# 3.net
KiCad netlist of a schematic drawn in Altium Designer
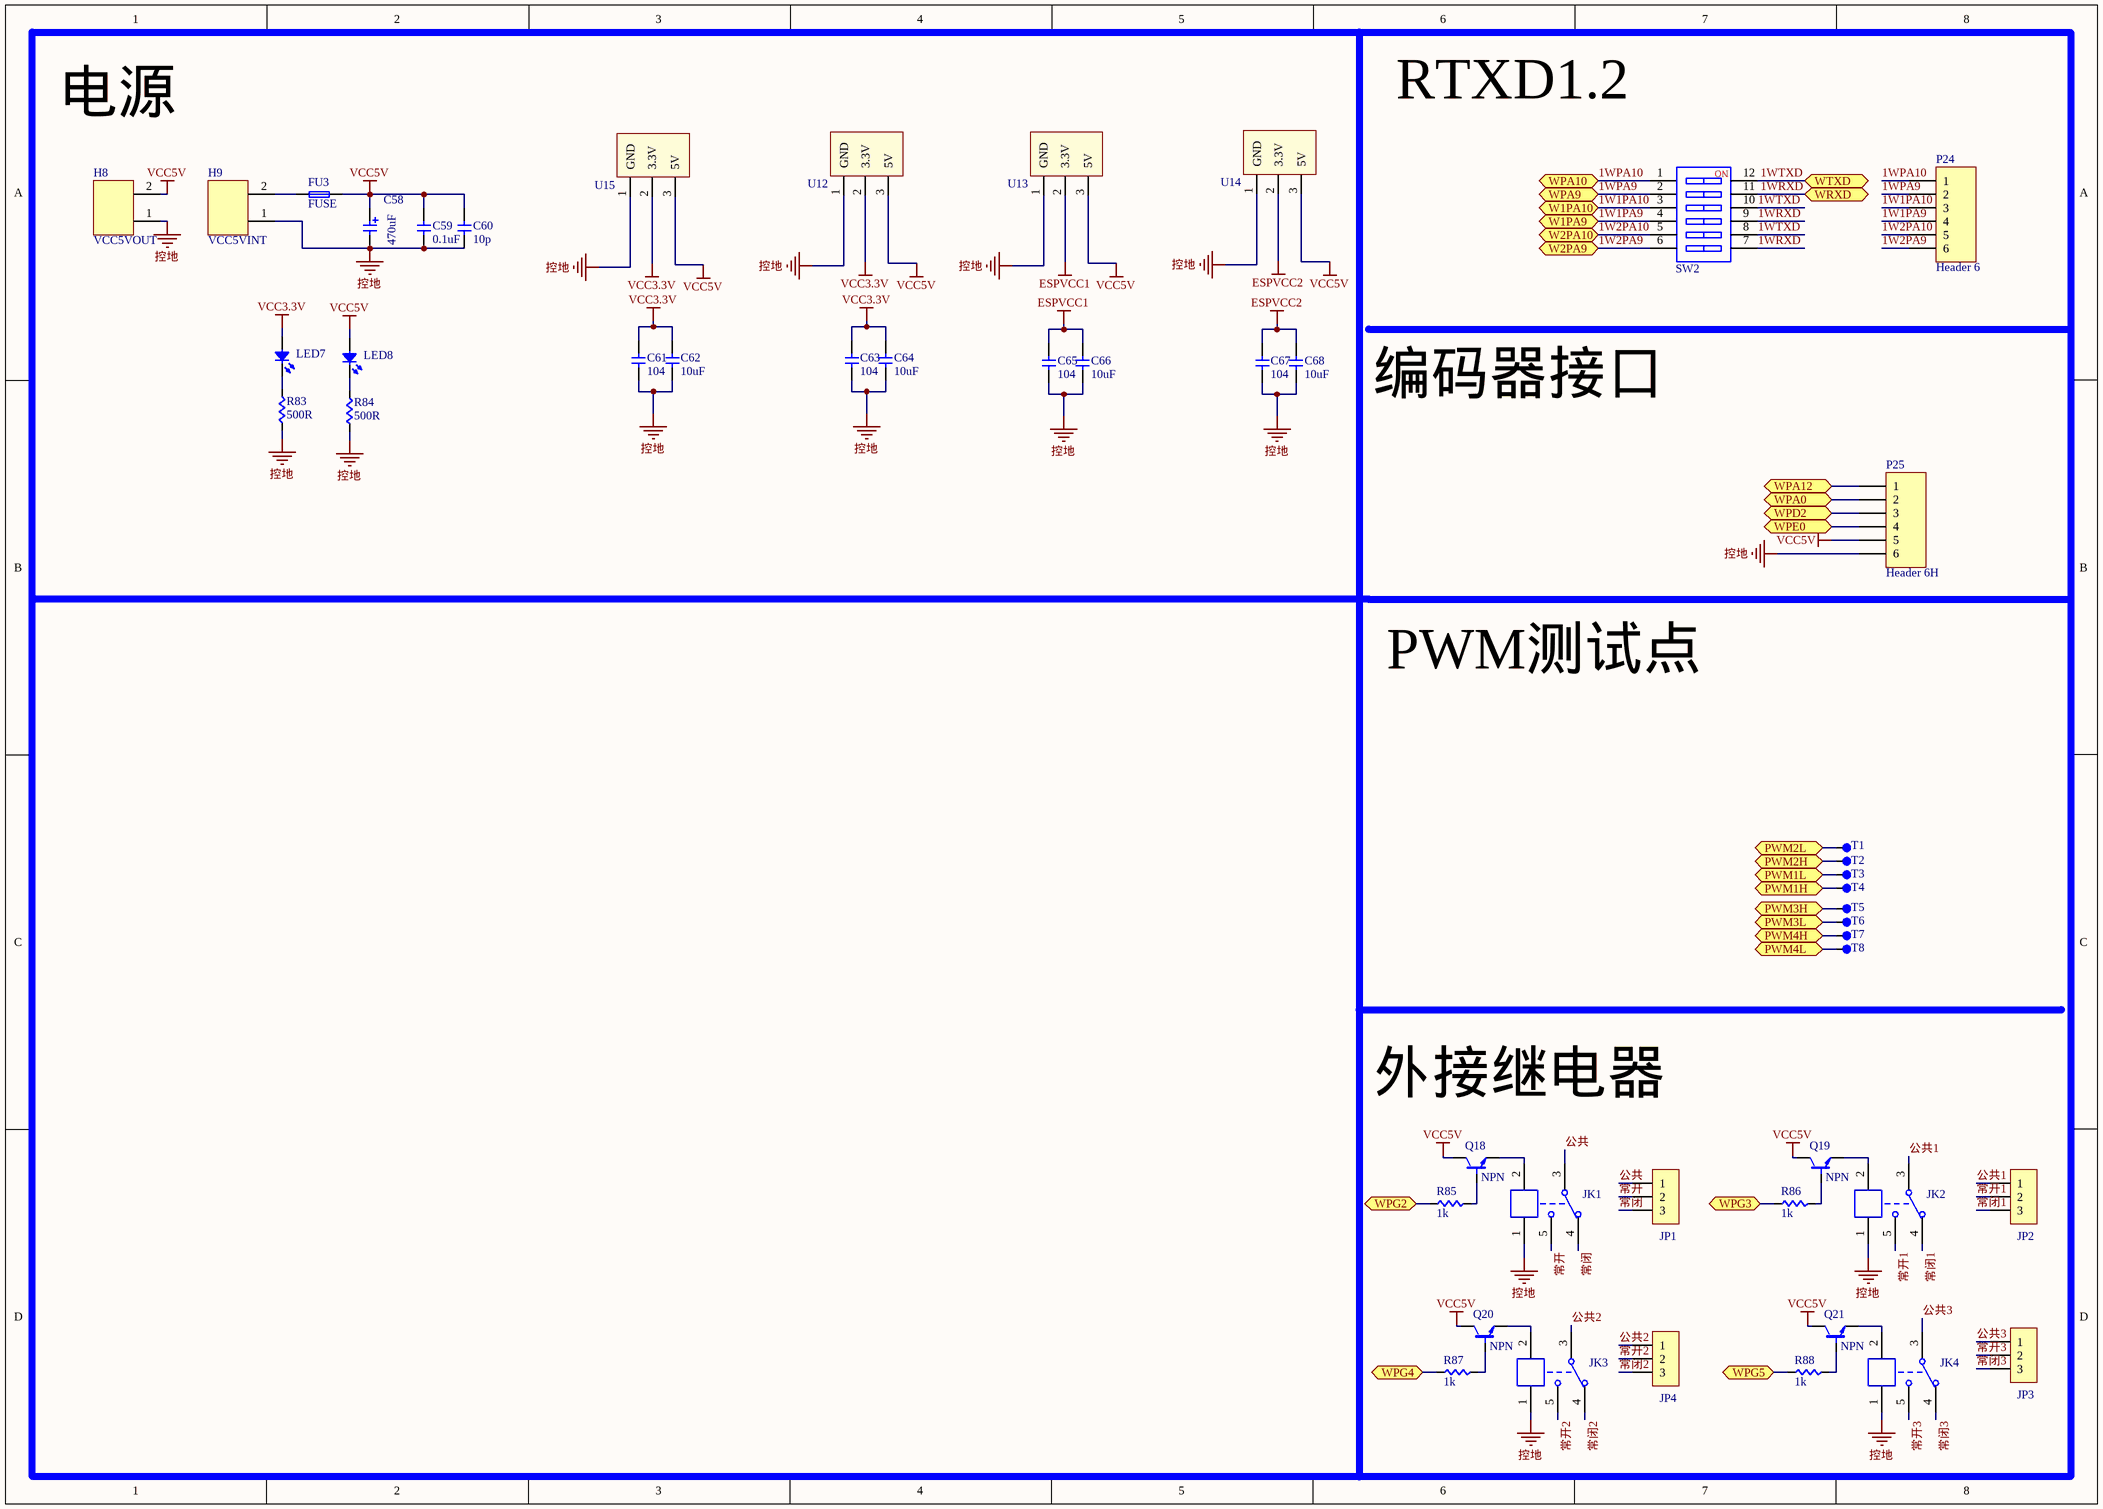
[diagram p0: 小车主板原理图3.SchDoc]

(export (version "E")
  (design (tool "Eeschema 10.0.6"))
  (components
    (comp (ref "C58")
      (value "470uF")
      (footprint "CD-8*8-2")
      (fields (field (name "PUBLISHER") "Altium Limited"))
      (libsource (lib "史福祥库") (part "C+"))
    )
    (comp (ref "C59") (value "0.1uF") (footprint "0805C") (libsource (lib "史福祥库") (part "C")))
    (comp (ref "C60") (value "10p") (footprint "0805C") (libsource (lib "史福祥库") (part "C")))
    (comp (ref "C61") (value "104") (footprint "0805C") (libsource (lib "史福祥库") (part "C")))
    (comp (ref "C62") (value "10uF") (footprint "0805C") (libsource (lib "史福祥库") (part "C")))
    (comp (ref "C63") (value "104") (footprint "0805C") (libsource (lib "史福祥库") (part "C")))
    (comp (ref "C64") (value "10uF") (footprint "0805C") (libsource (lib "史福祥库") (part "C")))
    (comp (ref "C65") (value "104") (footprint "0805C") (libsource (lib "史福祥库") (part "C")))
    (comp (ref "C66") (value "10uF") (footprint "0805C") (libsource (lib "史福祥库") (part "C")))
    (comp (ref "C67") (value "104") (footprint "0805C") (libsource (lib "史福祥库") (part "C")))
    (comp (ref "C68") (value "10uF") (footprint "0805C") (libsource (lib "史福祥库") (part "C")))
    (comp (ref "FU3") (value "FUSE") (footprint "1206") (libsource (lib "史福祥库") (part "FUSE")))
    (comp (ref "H8") (value "VCC5VOUT") (footprint "KF301接线端子") (libsource (lib "史福祥库") (part "KF301 接线端子")))
    (comp (ref "H9") (value "VCC5VINT") (footprint "KF301接线端子") (libsource (lib "史福祥库") (part "KF301 接线端子")))
    (comp (ref "JK1")
      (value "~")
      (footprint "SRD-C_B")
      (description "5V单路双控继电器")
      (fields (field (name "版权归属") "源创客"))
      (libsource (lib "继电器") (part "SRD-05VDC-SL-C"))
    )
    (comp (ref "JK2")
      (value "~")
      (footprint "SRD-C_B")
      (description "5V单路双控继电器")
      (fields (field (name "版权归属") "源创客"))
      (libsource (lib "继电器") (part "SRD-05VDC-SL-C"))
    )
    (comp (ref "JK3")
      (value "~")
      (footprint "SRD-C_B")
      (description "5V单路双控继电器")
      (fields (field (name "版权归属") "源创客"))
      (libsource (lib "继电器") (part "SRD-05VDC-SL-C"))
    )
    (comp (ref "JK4")
      (value "~")
      (footprint "SRD-C_B")
      (description "5V单路双控继电器")
      (fields (field (name "版权归属") "源创客"))
      (libsource (lib "继电器") (part "SRD-05VDC-SL-C"))
    )
    (comp (ref "JP1")
      (value "HDR-1X3")
      (footprint "KF301-3P")
      (description "3P接插件")
      (fields (field (name "版权归属") "源创客"))
      (libsource (lib "接插件") (part "Header 3"))
    )
    (comp (ref "JP2")
      (value "HDR-1X3")
      (footprint "KF301-3P")
      (description "3P接插件")
      (fields (field (name "版权归属") "源创客"))
      (libsource (lib "接插件") (part "Header 3"))
    )
    (comp (ref "JP3")
      (value "HDR-1X3")
      (footprint "KF301-3P")
      (description "3P接插件")
      (fields (field (name "版权归属") "源创客"))
      (libsource (lib "接插件") (part "Header 3"))
    )
    (comp (ref "JP4")
      (value "HDR-1X3")
      (footprint "KF301-3P")
      (description "3P接插件")
      (fields (field (name "版权归属") "源创客"))
      (libsource (lib "接插件") (part "Header 3"))
    )
    (comp (ref "LED7")
      (value "LED")
      (footprint "0805D")
      (fields (field (name "PUBLISHER") "Altium Limited"))
      (libsource (lib "史福祥库") (part "LED"))
    )
    (comp (ref "LED8")
      (value "LED")
      (footprint "0805D")
      (fields (field (name "PUBLISHER") "Altium Limited"))
      (libsource (lib "史福祥库") (part "LED"))
    )
    (comp (ref "P24")
      (value "Header 6")
      (footprint "HDR1X6")
      (description "Header, 6-Pin")
      (fields (field (name "PUBLISHER") "Altium Limited"))
      (libsource (lib "Miscellaneous Connectors") (part "Header 6"))
    )
    (comp (ref "P25")
      (value "Header 6H")
      (footprint "PZ_XH-2.54-6P")
      (description "Header, 6-Pin, Right Angle")
      (fields (field (name "PUBLISHER") "Altium Limited"))
      (libsource (lib "Miscellaneous Connectors") (part "Header 6H"))
    )
    (comp (ref "Q18") (value "NPN") (footprint "SOT-23") (libsource (lib "史福祥库") (part "NPN")))
    (comp (ref "Q19") (value "NPN") (footprint "SOT-23") (libsource (lib "史福祥库") (part "NPN")))
    (comp (ref "Q20") (value "NPN") (footprint "SOT-23") (libsource (lib "史福祥库") (part "NPN")))
    (comp (ref "Q21") (value "NPN") (footprint "SOT-23") (libsource (lib "史福祥库") (part "NPN")))
    (comp (ref "R83") (value "500R") (footprint "0805") (libsource (lib "史福祥库") (part "Res")))
    (comp (ref "R84") (value "500R") (footprint "0805") (libsource (lib "史福祥库") (part "Res")))
    (comp (ref "R85") (value "1k") (footprint "0805") (libsource (lib "史福祥库") (part "Res")))
    (comp (ref "R86") (value "1k") (footprint "0805") (libsource (lib "史福祥库") (part "Res")))
    (comp (ref "R87") (value "1k") (footprint "0805") (libsource (lib "史福祥库") (part "Res")))
    (comp (ref "R88") (value "1k") (footprint "0805") (libsource (lib "史福祥库") (part "Res")))
    (comp (ref "SW2")
      (value "CSW-6P")
      (footprint "CSW DIP-6P")
      (description "6路编码开关")
      (fields (field (name "版权归属") "源创客"))
      (libsource (lib "史福祥库") (part "CSW-6P"))
    )
    (comp (ref "T1") (value "1 测试点") (footprint "SIP1-1*1") (libsource (lib "史福祥库") (part "1 测试点")))
    (comp (ref "T2") (value "1 测试点") (footprint "SIP1-1*1") (libsource (lib "史福祥库") (part "1 测试点")))
    (comp (ref "T3") (value "1 测试点") (footprint "SIP1-1*1") (libsource (lib "史福祥库") (part "1 测试点")))
    (comp (ref "T4") (value "1 测试点") (footprint "SIP1-1*1") (libsource (lib "史福祥库") (part "1 测试点")))
    (comp (ref "T5") (value "1 测试点") (footprint "SIP1-1*1") (libsource (lib "史福祥库") (part "1 测试点")))
    (comp (ref "T6") (value "1 测试点") (footprint "SIP1-1*1") (libsource (lib "史福祥库") (part "1 测试点")))
    (comp (ref "T7") (value "1 测试点") (footprint "SIP1-1*1") (libsource (lib "史福祥库") (part "1 测试点")))
    (comp (ref "T8") (value "1 测试点") (footprint "SIP1-1*1") (libsource (lib "史福祥库") (part "1 测试点")))
    (comp (ref "U12") (value "LM1117") (footprint "SOT-223") (libsource (lib "史福祥库") (part "LM1117")))
    (comp (ref "U13") (value "LM1117") (footprint "SOT-223") (libsource (lib "史福祥库") (part "LM1117")))
    (comp (ref "U14") (value "LM1117") (footprint "SOT-223") (libsource (lib "史福祥库") (part "LM1117")))
    (comp (ref "U15") (value "LM1117") (footprint "SOT-223") (libsource (lib "史福祥库") (part "LM1117")))
  )
  (nets
    (net (code "1") (name "/1W1PA9") (class "Default")
      (node (ref "P24") (pin "4") (pinfunction "4_4") (pintype "passive"))
      (node (ref "SW2") (pin "4") (pinfunction "4_4") (pintype "passive"))
    )
    (net (code "2") (name "/1W1PA10") (class "Default")
      (node (ref "P24") (pin "3") (pinfunction "3_3") (pintype "passive"))
      (node (ref "SW2") (pin "3") (pinfunction "3_3") (pintype "passive"))
    )
    (net (code "3") (name "/1W2PA9") (class "Default")
      (node (ref "P24") (pin "6") (pinfunction "6_6") (pintype "passive"))
      (node (ref "SW2") (pin "6") (pinfunction "6_6") (pintype "passive"))
    )
    (net (code "4") (name "/1W2PA10") (class "Default")
      (node (ref "P24") (pin "5") (pinfunction "5_5") (pintype "passive"))
      (node (ref "SW2") (pin "5") (pinfunction "5_5") (pintype "passive"))
    )
    (net (code "5") (name "/1WPA9") (class "Default")
      (node (ref "P24") (pin "2") (pinfunction "2_2") (pintype "passive"))
      (node (ref "SW2") (pin "2") (pinfunction "2_2") (pintype "passive"))
    )
    (net (code "6") (name "/1WPA10") (class "Default")
      (node (ref "P24") (pin "1") (pinfunction "1_1") (pintype "passive"))
      (node (ref "SW2") (pin "1") (pinfunction "1_1") (pintype "passive"))
    )
    (net (code "7") (name "/1WRXD") (class "Default")
      (node (ref "SW2") (pin "11") (pinfunction "11_11") (pintype "passive"))
      (node (ref "SW2") (pin "7") (pinfunction "7_7") (pintype "passive"))
      (node (ref "SW2") (pin "9") (pinfunction "9_9") (pintype "passive"))
    )
    (net (code "8") (name "/1WTXD") (class "Default")
      (node (ref "SW2") (pin "10") (pinfunction "10_10") (pintype "passive"))
      (node (ref "SW2") (pin "12") (pinfunction "12_12") (pintype "passive"))
      (node (ref "SW2") (pin "8") (pinfunction "8_8") (pintype "passive"))
    )
    (net (code "9") (name "/PWM1H") (class "Default") (node (ref "T4") (pin "1") (pintype "passive")))
    (net (code "10") (name "/PWM1L") (class "Default") (node (ref "T3") (pin "1") (pintype "passive")))
    (net (code "11") (name "/PWM2H") (class "Default") (node (ref "T2") (pin "1") (pintype "passive")))
    (net (code "12") (name "/PWM2L") (class "Default") (node (ref "T1") (pin "1") (pintype "passive")))
    (net (code "13") (name "/PWM3H") (class "Default") (node (ref "T5") (pin "1") (pintype "passive")))
    (net (code "14") (name "/PWM3L") (class "Default") (node (ref "T6") (pin "1") (pintype "passive")))
    (net (code "15") (name "/PWM4H") (class "Default") (node (ref "T7") (pin "1") (pintype "passive")))
    (net (code "16") (name "/PWM4L") (class "Default") (node (ref "T8") (pin "1") (pintype "passive")))
    (net (code "17") (name "/WPA0") (class "Default")
      (node (ref "P25") (pin "2") (pinfunction "2_2") (pintype "passive"))
    )
    (net (code "18") (name "/WPA12") (class "Default")
      (node (ref "P25") (pin "1") (pinfunction "1_1") (pintype "passive"))
    )
    (net (code "19") (name "/WPD2") (class "Default")
      (node (ref "P25") (pin "3") (pinfunction "3_3") (pintype "passive"))
    )
    (net (code "20") (name "/WPE0") (class "Default")
      (node (ref "P25") (pin "4") (pinfunction "4_4") (pintype "passive"))
    )
    (net (code "21") (name "/WPG2") (class "Default")
      (node (ref "R85") (pin "1") (pinfunction "1_1") (pintype "passive"))
    )
    (net (code "22") (name "/WPG3") (class "Default")
      (node (ref "R86") (pin "1") (pinfunction "1_1") (pintype "passive"))
    )
    (net (code "23") (name "/WPG4") (class "Default")
      (node (ref "R87") (pin "1") (pinfunction "1_1") (pintype "passive"))
    )
    (net (code "24") (name "/WPG5") (class "Default")
      (node (ref "R88") (pin "1") (pinfunction "1_1") (pintype "passive"))
    )
    (net (code "25") (name "/公共") (class "Default")
      (node (ref "JK1") (pin "3") (pinfunction "3_3") (pintype "passive"))
      (node (ref "JP1") (pin "1") (pinfunction "1_1") (pintype "passive"))
    )
    (net (code "26") (name "/公共1") (class "Default")
      (node (ref "JK2") (pin "3") (pinfunction "3_3") (pintype "passive"))
      (node (ref "JP2") (pin "1") (pinfunction "1_1") (pintype "passive"))
    )
    (net (code "27") (name "/公共2") (class "Default")
      (node (ref "JK3") (pin "3") (pinfunction "3_3") (pintype "passive"))
      (node (ref "JP4") (pin "1") (pinfunction "1_1") (pintype "passive"))
    )
    (net (code "28") (name "/公共3") (class "Default")
      (node (ref "JK4") (pin "3") (pinfunction "3_3") (pintype "passive"))
      (node (ref "JP3") (pin "1") (pinfunction "1_1") (pintype "passive"))
    )
    (net (code "29") (name "/常开") (class "Default")
      (node (ref "JK1") (pin "5") (pinfunction "5_5") (pintype "passive"))
      (node (ref "JP1") (pin "2") (pinfunction "2_2") (pintype "passive"))
    )
    (net (code "30") (name "/常开1") (class "Default")
      (node (ref "JK2") (pin "5") (pinfunction "5_5") (pintype "passive"))
      (node (ref "JP2") (pin "2") (pinfunction "2_2") (pintype "passive"))
    )
    (net (code "31") (name "/常开2") (class "Default")
      (node (ref "JK3") (pin "5") (pinfunction "5_5") (pintype "passive"))
      (node (ref "JP4") (pin "2") (pinfunction "2_2") (pintype "passive"))
    )
    (net (code "32") (name "/常开3") (class "Default")
      (node (ref "JK4") (pin "5") (pinfunction "5_5") (pintype "passive"))
      (node (ref "JP3") (pin "2") (pinfunction "2_2") (pintype "passive"))
    )
    (net (code "33") (name "/常闭") (class "Default")
      (node (ref "JK1") (pin "4") (pinfunction "4_4") (pintype "passive"))
      (node (ref "JP1") (pin "3") (pinfunction "3_3") (pintype "passive"))
    )
    (net (code "34") (name "/常闭1") (class "Default")
      (node (ref "JK2") (pin "4") (pinfunction "4_4") (pintype "passive"))
      (node (ref "JP2") (pin "3") (pinfunction "3_3") (pintype "passive"))
    )
    (net (code "35") (name "/常闭2") (class "Default")
      (node (ref "JK3") (pin "4") (pinfunction "4_4") (pintype "passive"))
      (node (ref "JP4") (pin "3") (pinfunction "3_3") (pintype "passive"))
    )
    (net (code "36") (name "/常闭3") (class "Default")
      (node (ref "JK4") (pin "4") (pinfunction "4_4") (pintype "passive"))
      (node (ref "JP3") (pin "3") (pinfunction "3_3") (pintype "passive"))
    )
    (net (code "37") (name "ESPVCC1") (class "Default")
      (node (ref "C65") (pin "2") (pinfunction "2_2") (pintype "passive"))
      (node (ref "C66") (pin "2") (pinfunction "2_2") (pintype "passive"))
      (node (ref "U13") (pin "2") (pinfunction "3.3V_2") (pintype "passive"))
    )
    (net (code "38") (name "ESPVCC2") (class "Default")
      (node (ref "C67") (pin "2") (pinfunction "2_2") (pintype "passive"))
      (node (ref "C68") (pin "2") (pinfunction "2_2") (pintype "passive"))
      (node (ref "U14") (pin "2") (pinfunction "3.3V_2") (pintype "passive"))
    )
    (net (code "39") (name "Net-(FU3-Pad1)") (class "Default")
      (node (ref "FU3") (pin "1") (pinfunction "1_1") (pintype "passive"))
      (node (ref "H9") (pin "2") (pintype "passive"))
    )
    (net (code "40") (name "Net-(LED7-K)") (class "Default")
      (node (ref "LED7") (pin "2") (pinfunction "K_2") (pintype "passive"))
      (node (ref "R83") (pin "2") (pinfunction "2_2") (pintype "passive"))
    )
    (net (code "41") (name "Net-(LED8-K)") (class "Default")
      (node (ref "LED8") (pin "2") (pinfunction "K_2") (pintype "passive"))
      (node (ref "R84") (pin "2") (pinfunction "2_2") (pintype "passive"))
    )
    (net (code "42") (name "Net-(Q18-b)") (class "Default")
      (node (ref "Q18") (pin "3") (pinfunction "b_3") (pintype "passive"))
      (node (ref "R85") (pin "2") (pinfunction "2_2") (pintype "passive"))
    )
    (net (code "43") (name "Net-(Q18-e)") (class "Default")
      (node (ref "JK1") (pin "2") (pinfunction "2_2") (pintype "passive"))
      (node (ref "Q18") (pin "2") (pinfunction "e_2") (pintype "passive"))
    )
    (net (code "44") (name "Net-(Q19-b)") (class "Default")
      (node (ref "Q19") (pin "3") (pinfunction "b_3") (pintype "passive"))
      (node (ref "R86") (pin "2") (pinfunction "2_2") (pintype "passive"))
    )
    (net (code "45") (name "Net-(Q19-e)") (class "Default")
      (node (ref "JK2") (pin "2") (pinfunction "2_2") (pintype "passive"))
      (node (ref "Q19") (pin "2") (pinfunction "e_2") (pintype "passive"))
    )
    (net (code "46") (name "Net-(Q20-b)") (class "Default")
      (node (ref "Q20") (pin "3") (pinfunction "b_3") (pintype "passive"))
      (node (ref "R87") (pin "2") (pinfunction "2_2") (pintype "passive"))
    )
    (net (code "47") (name "Net-(Q20-e)") (class "Default")
      (node (ref "JK3") (pin "2") (pinfunction "2_2") (pintype "passive"))
      (node (ref "Q20") (pin "2") (pinfunction "e_2") (pintype "passive"))
    )
    (net (code "48") (name "Net-(Q21-b)") (class "Default")
      (node (ref "Q21") (pin "3") (pinfunction "b_3") (pintype "passive"))
      (node (ref "R88") (pin "2") (pinfunction "2_2") (pintype "passive"))
    )
    (net (code "49") (name "Net-(Q21-e)") (class "Default")
      (node (ref "JK4") (pin "2") (pinfunction "2_2") (pintype "passive"))
      (node (ref "Q21") (pin "2") (pinfunction "e_2") (pintype "passive"))
    )
    (net (code "50") (name "VCC3.3V") (class "Default")
      (node (ref "C61") (pin "2") (pinfunction "2_2") (pintype "passive"))
      (node (ref "C62") (pin "2") (pinfunction "2_2") (pintype "passive"))
      (node (ref "C63") (pin "2") (pinfunction "2_2") (pintype "passive"))
      (node (ref "C64") (pin "2") (pinfunction "2_2") (pintype "passive"))
      (node (ref "LED7") (pin "1") (pinfunction "A_1") (pintype "passive"))
      (node (ref "U12") (pin "2") (pinfunction "3.3V_2") (pintype "passive"))
      (node (ref "U15") (pin "2") (pinfunction "3.3V_2") (pintype "passive"))
    )
    (net (code "51") (name "VCC5V") (class "Default")
      (node (ref "C58") (pin "1") (pinfunction "1_1") (pintype "passive"))
      (node (ref "C59") (pin "2") (pinfunction "2_2") (pintype "passive"))
      (node (ref "C60") (pin "2") (pinfunction "2_2") (pintype "passive"))
      (node (ref "FU3") (pin "2") (pinfunction "2_2") (pintype "passive"))
      (node (ref "H8") (pin "2") (pintype "passive"))
      (node (ref "LED8") (pin "1") (pinfunction "A_1") (pintype "passive"))
      (node (ref "P25") (pin "5") (pinfunction "5_5") (pintype "passive"))
      (node (ref "Q18") (pin "1") (pinfunction "c_1") (pintype "passive"))
      (node (ref "Q19") (pin "1") (pinfunction "c_1") (pintype "passive"))
      (node (ref "Q20") (pin "1") (pinfunction "c_1") (pintype "passive"))
      (node (ref "Q21") (pin "1") (pinfunction "c_1") (pintype "passive"))
      (node (ref "U12") (pin "3") (pinfunction "5V_3") (pintype "passive"))
      (node (ref "U13") (pin "3") (pinfunction "5V_3") (pintype "passive"))
      (node (ref "U14") (pin "3") (pinfunction "5V_3") (pintype "passive"))
      (node (ref "U15") (pin "3") (pinfunction "5V_3") (pintype "passive"))
    )
    (net (code "52") (name "控地") (class "Default")
      (node (ref "C58") (pin "2") (pinfunction "2_2") (pintype "passive"))
      (node (ref "C59") (pin "1") (pinfunction "1_1") (pintype "passive"))
      (node (ref "C60") (pin "1") (pinfunction "1_1") (pintype "passive"))
      (node (ref "C61") (pin "1") (pinfunction "1_1") (pintype "passive"))
      (node (ref "C62") (pin "1") (pinfunction "1_1") (pintype "passive"))
      (node (ref "C63") (pin "1") (pinfunction "1_1") (pintype "passive"))
      (node (ref "C64") (pin "1") (pinfunction "1_1") (pintype "passive"))
      (node (ref "C65") (pin "1") (pinfunction "1_1") (pintype "passive"))
      (node (ref "C66") (pin "1") (pinfunction "1_1") (pintype "passive"))
      (node (ref "C67") (pin "1") (pinfunction "1_1") (pintype "passive"))
      (node (ref "C68") (pin "1") (pinfunction "1_1") (pintype "passive"))
      (node (ref "H8") (pin "1") (pintype "passive"))
      (node (ref "H9") (pin "1") (pintype "passive"))
      (node (ref "JK1") (pin "1") (pinfunction "1_1") (pintype "passive"))
      (node (ref "JK2") (pin "1") (pinfunction "1_1") (pintype "passive"))
      (node (ref "JK3") (pin "1") (pinfunction "1_1") (pintype "passive"))
      (node (ref "JK4") (pin "1") (pinfunction "1_1") (pintype "passive"))
      (node (ref "P25") (pin "6") (pinfunction "6_6") (pintype "passive"))
      (node (ref "R83") (pin "1") (pinfunction "1_1") (pintype "passive"))
      (node (ref "R84") (pin "1") (pinfunction "1_1") (pintype "passive"))
      (node (ref "U12") (pin "1") (pinfunction "GND_1") (pintype "passive"))
      (node (ref "U13") (pin "1") (pinfunction "GND_1") (pintype "passive"))
      (node (ref "U14") (pin "1") (pinfunction "GND_1") (pintype "passive"))
      (node (ref "U15") (pin "1") (pinfunction "GND_1") (pintype "passive"))
    )
  )
)
